# Power.net
KiCad netlist of a schematic drawn in Altium Designer
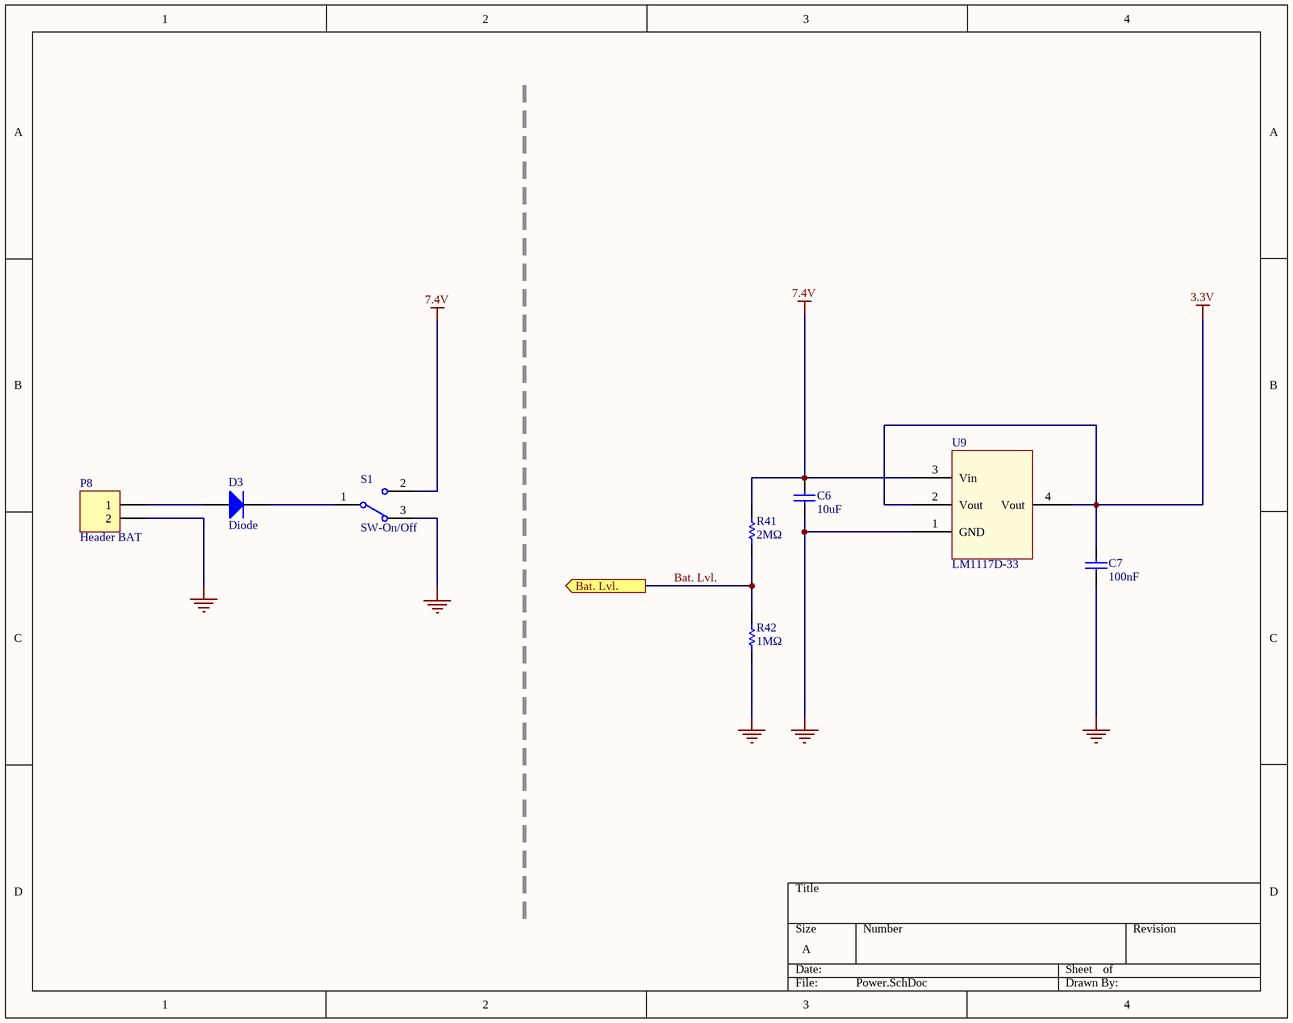
[diagram p0: Power.SchDoc]

(export (version "E")
  (design (tool "Eeschema 10.0.6"))
  (components
    (comp (ref "C6")
      (value "10uF")
      (footprint "C0603")
      (description "Capacitor")
      (fields (field (name "MANUFACTURER") "MURATA") (field (name "PUBLISHER") "Altium Limited"))
      (libsource (lib "Miscellaneous Devices") (part "Cap"))
    )
    (comp (ref "C7")
      (value "100nF")
      (footprint "C0603")
      (description "Capacitor")
      (fields (field (name "MANUFACTURER") "MURATA") (field (name "PUBLISHER") "Altium Limited"))
      (libsource (lib "Miscellaneous Devices") (part "Cap"))
    )
    (comp (ref "D3")
      (value "Diode")
      (footprint "SMC")
      (fields (field (name "PUBLISHER") "Altium Limited"))
      (libsource (lib "Miscellaneous Devices") (part "Diode"))
    )
    (comp (ref "P8")
      (value "Header BAT")
      (footprint "BORNIER")
      (description "Header, 2-Pin")
      (fields
        (field (name "MANUFACTURER") "BUCHANAN - TE CONNECTIVITY")
        (field (name "PUBLISHER") "Altium Limited")
      )
      (libsource (lib "Miscellaneous Connectors") (part "Header 2"))
    )
    (comp (ref "R41")
      (value "2MΩ")
      (footprint "R0603")
      (description "Resistor")
      (fields (field (name "MANUFACTURER") "MULTICOMP") (field (name "PUBLISHER") "Altium Limited"))
      (libsource (lib "Miscellaneous Devices") (part "Res1"))
    )
    (comp (ref "R42")
      (value "1MΩ")
      (footprint "R0603")
      (description "Resistor")
      (fields (field (name "MANUFACTURER") "MULTICOMP") (field (name "PUBLISHER") "Altium Limited"))
      (libsource (lib "Miscellaneous Devices") (part "Res1"))
    )
    (comp (ref "S1")
      (value "SW-On/Off")
      (footprint "Switch on/off")
      (description "SPDT Subminiature Toggle Switch, Right Angle Mounting, Vertical Actuation")
      (fields (field (name "MANUFACTURER") "EOZ") (field (name "PUBLISHER") "Altium Limited"))
      (libsource (lib "Miscellaneous Devices") (part "SW-SPDT"))
    )
    (comp (ref "U9")
      (value "LM1117D-33")
      (footprint "VoltReg3.3V")
      (description "Battery")
      (fields (field (name "MANUFACTURER") "TEXAS INSTRUMENTS"))
      (libsource (lib "Electroplant") (part "LM1117D-33"))
    )
  )
  (nets
    (net (code "1") (name "/Bat. Lvl.") (class "Default")
      (node (ref "R41") (pin "1") (pinfunction "1_1") (pintype "passive"))
      (node (ref "R42") (pin "2") (pinfunction "2_2") (pintype "passive"))
    )
    (net (code "2") (name "3.3V") (class "Default")
      (node (ref "C7") (pin "2") (pinfunction "2_2") (pintype "passive"))
      (node (ref "U9") (pin "2") (pinfunction "Vout_2") (pintype "passive"))
      (node (ref "U9") (pin "4") (pinfunction "Vout_4") (pintype "passive"))
    )
    (net (code "3") (name "7.4V") (class "Default")
      (node (ref "C6") (pin "2") (pinfunction "2_2") (pintype "passive"))
      (node (ref "R41") (pin "2") (pinfunction "2_2") (pintype "passive"))
      (node (ref "S1") (pin "2") (pinfunction "2_2") (pintype "passive"))
      (node (ref "U9") (pin "3") (pinfunction "Vin_3") (pintype "passive"))
    )
    (net (code "4") (name "GND") (class "Default")
      (node (ref "C6") (pin "1") (pinfunction "1_1") (pintype "passive"))
      (node (ref "C7") (pin "1") (pinfunction "1_1") (pintype "passive"))
      (node (ref "P8") (pin "2") (pinfunction "2_2") (pintype "passive"))
      (node (ref "R42") (pin "1") (pinfunction "1_1") (pintype "passive"))
      (node (ref "S1") (pin "3") (pinfunction "3_3") (pintype "passive"))
      (node (ref "U9") (pin "1") (pinfunction "GND_1") (pintype "passive"))
    )
    (net (code "5") (name "Net-(D3-A)") (class "Default")
      (node (ref "D3") (pin "1") (pinfunction "A_1") (pintype "passive"))
      (node (ref "P8") (pin "1") (pinfunction "1_1") (pintype "passive"))
    )
    (net (code "6") (name "Net-(D3-K)") (class "Default")
      (node (ref "D3") (pin "2") (pinfunction "K_2") (pintype "passive"))
      (node (ref "S1") (pin "1") (pinfunction "1_1") (pintype "passive"))
    )
  )
)
